# Sheet1.net
KiCad netlist of a schematic drawn in Altium Designer
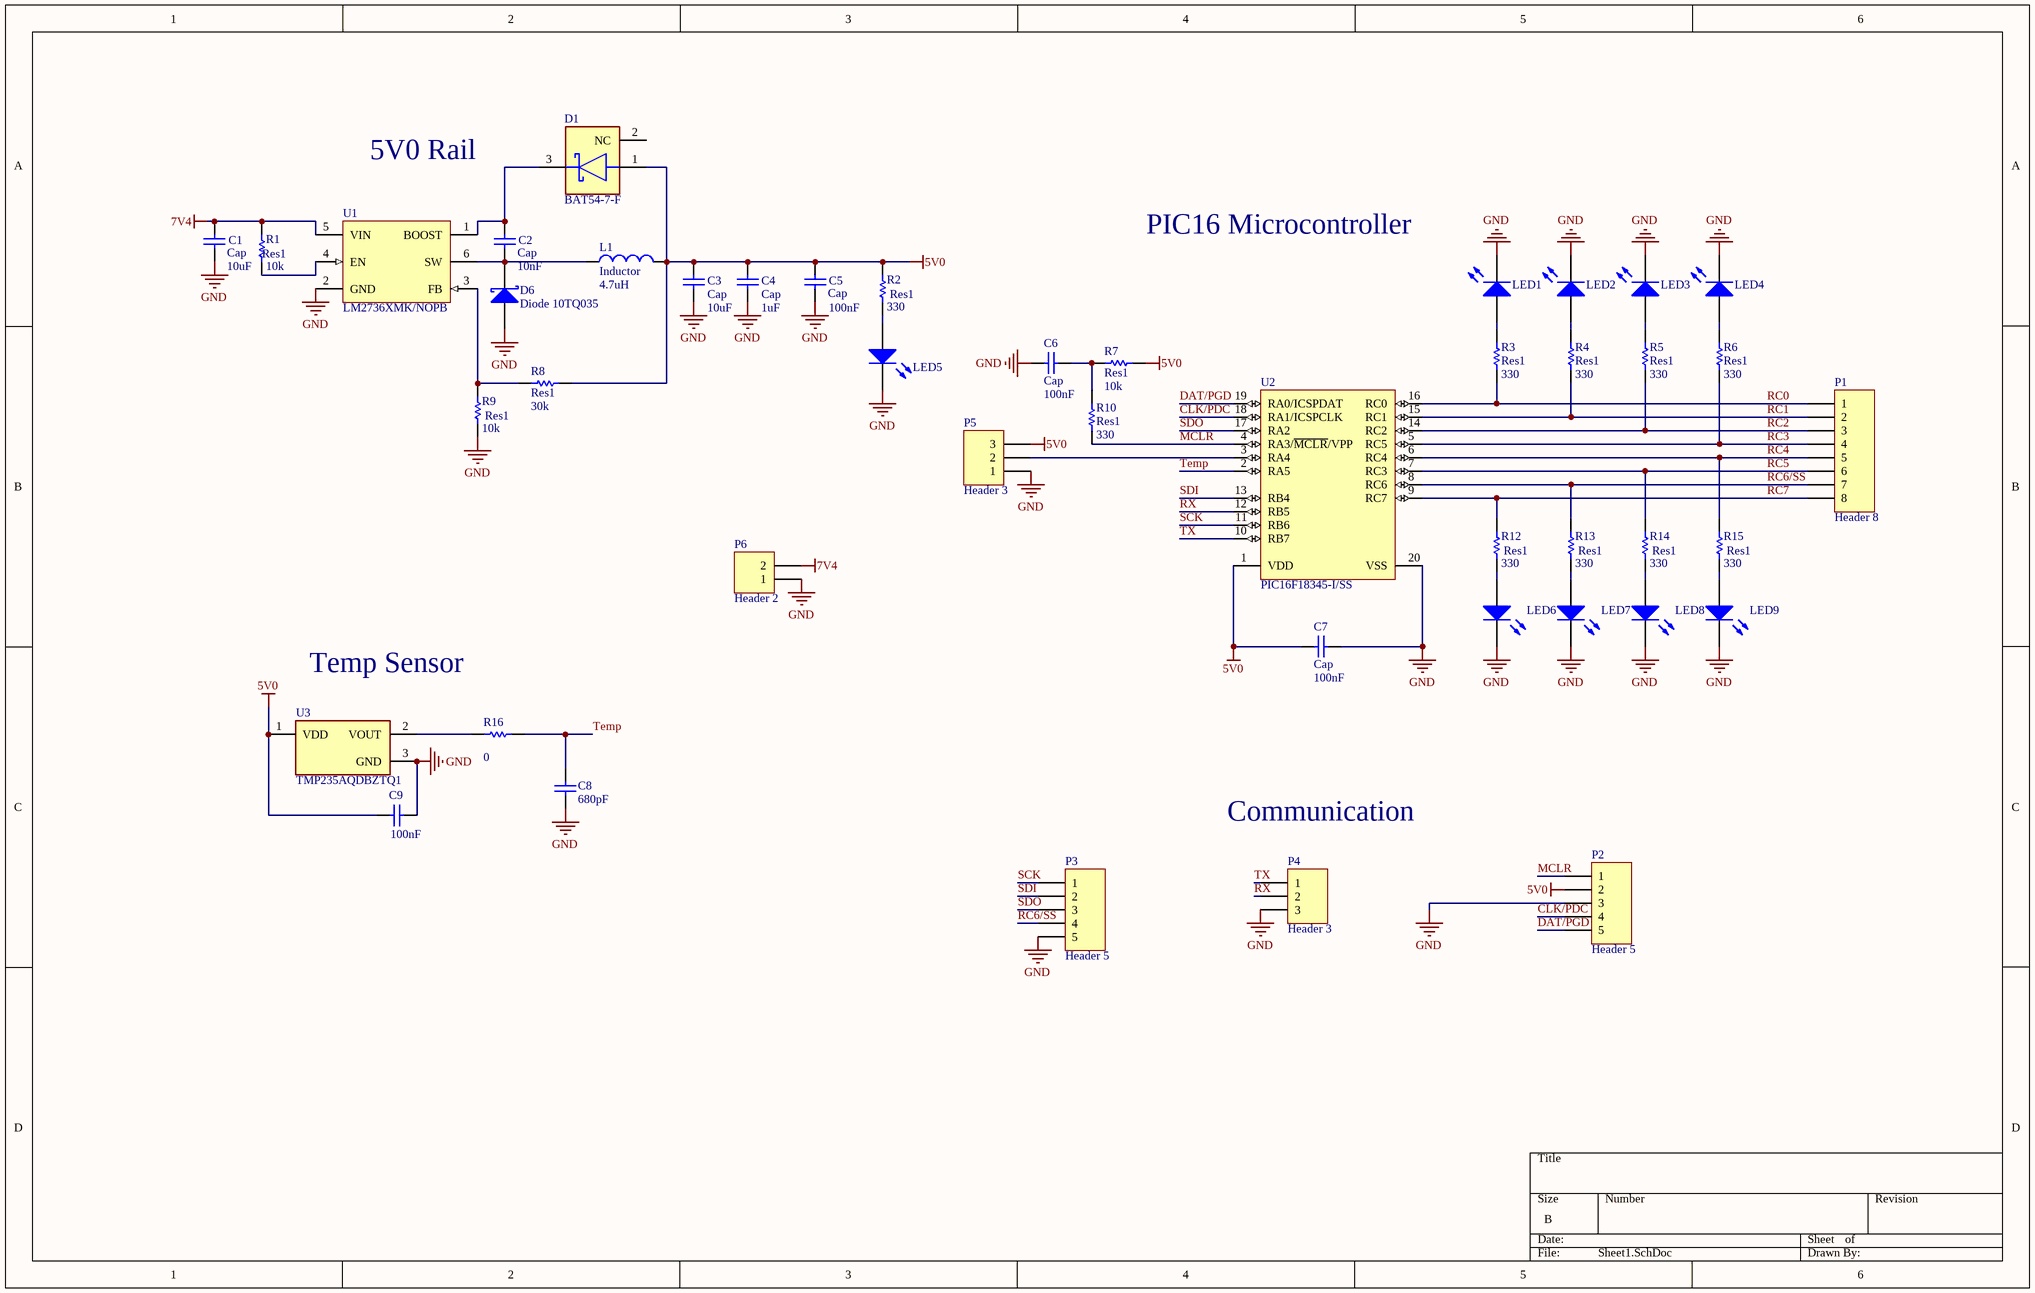
[diagram p0: Sheet1.SchDoc]

(export (version "E")
  (design (tool "Eeschema 10.0.6"))
  (components
    (comp (ref "C1")
      (value "Cap")
      (footprint "6-0805_M")
      (description "Capacitor")
      (fields (field (name "ALTIUM_VALUE") "10uF") (field (name "PUBLISHER") "Altium Limited"))
      (libsource (lib "Miscellaneous Devices") (part "Cap"))
    )
    (comp (ref "C2")
      (value "Cap")
      (footprint "6-0805_M")
      (description "Capacitor")
      (fields (field (name "ALTIUM_VALUE") "10nF") (field (name "PUBLISHER") "Altium Limited"))
      (libsource (lib "Miscellaneous Devices") (part "Cap"))
    )
    (comp (ref "C3")
      (value "Cap")
      (footprint "6-0805_M")
      (description "Capacitor")
      (fields (field (name "ALTIUM_VALUE") "10uF") (field (name "PUBLISHER") "Altium Limited"))
      (libsource (lib "Miscellaneous Devices") (part "Cap"))
    )
    (comp (ref "C4")
      (value "Cap")
      (footprint "6-0805_M")
      (description "Capacitor")
      (fields (field (name "ALTIUM_VALUE") "1uF") (field (name "PUBLISHER") "Altium Limited"))
      (libsource (lib "Miscellaneous Devices") (part "Cap"))
    )
    (comp (ref "C5")
      (value "Cap")
      (footprint "6-0805_M")
      (description "Capacitor")
      (fields (field (name "ALTIUM_VALUE") "100nF") (field (name "PUBLISHER") "Altium Limited"))
      (libsource (lib "Miscellaneous Devices") (part "Cap"))
    )
    (comp (ref "C6")
      (value "Cap")
      (footprint "6-0805_M")
      (description "Capacitor")
      (fields (field (name "ALTIUM_VALUE") "100nF") (field (name "PUBLISHER") "Altium Limited"))
      (libsource (lib "Miscellaneous Devices") (part "Cap"))
    )
    (comp (ref "C7")
      (value "Cap")
      (footprint "6-0805_M")
      (description "Capacitor")
      (fields (field (name "ALTIUM_VALUE") "100nF") (field (name "PUBLISHER") "Altium Limited"))
      (libsource (lib "Miscellaneous Devices") (part "Cap"))
    )
    (comp (ref "C8")
      (value "680pF")
      (footprint "6-0805_M")
      (description "Capacitor")
      (fields (field (name "Comment") "Cap") (field (name "PUBLISHER") "Altium Limited"))
      (libsource (lib "Miscellaneous Devices") (part "Cap"))
    )
    (comp (ref "C9")
      (value "100nF")
      (footprint "6-0805_M")
      (description "Capacitor")
      (fields (field (name "Comment") "Cap") (field (name "PUBLISHER") "Altium Limited"))
      (libsource (lib "Miscellaneous Devices") (part "Cap"))
    )
    (comp (ref "D1")
      (value "BAT54-7-F")
      (footprint "FP-SOT23-MFG")
      (description "DIODE SCHOTTKY 30V 200MA SOT23-3")
      (fields
        (field (name "MANUFACTURER") "Diodes Inc.")
        (field (name "OCTOPART") "https://octopart.com/bat54-7-f-diodes+inc.-39681803")
      )
      (libsource (lib "Altium Content Vault") (part "c46c961685e925f3e7b53c7fd0df730"))
    )
    (comp (ref "D6")
      (value "Diode 10TQ035")
      (footprint "CDBA5")
      (description "Schottky Rectifier")
      (fields (field (name "PUBLISHER") "Altium Limited"))
      (libsource (lib "Miscellaneous Devices") (part "Diode 10TQ035"))
    )
    (comp (ref "L1")
      (value "Inductor")
      (footprint "INDC2520X100N")
      (fields (field (name "ALTIUM_VALUE") "4.7uH") (field (name "PUBLISHER") "Altium Limited"))
      (libsource (lib "Miscellaneous Devices") (part "Inductor"))
    )
    (comp (ref "LED1")
      (value "150080BS75000")
      (footprint "0805_A")
      (description "SMD mono-color Chip LED, WL-SMCW, Blue")
      (fields (field (name "MANUFACTURER") "Wuerth Elektronik"))
      (libsource (lib "Altium Content Vault") (part "WE-LED_K1A2-2"))
    )
    (comp (ref "LED2")
      (value "150080BS75000")
      (footprint "0805_A")
      (description "SMD mono-color Chip LED, WL-SMCW, Blue")
      (fields (field (name "MANUFACTURER") "Wuerth Elektronik"))
      (libsource (lib "Altium Content Vault") (part "WE-LED_K1A2-2"))
    )
    (comp (ref "LED3")
      (value "150080BS75000")
      (footprint "0805_A")
      (description "SMD mono-color Chip LED, WL-SMCW, Blue")
      (fields (field (name "MANUFACTURER") "Wuerth Elektronik"))
      (libsource (lib "Altium Content Vault") (part "WE-LED_K1A2-2"))
    )
    (comp (ref "LED4")
      (value "150080BS75000")
      (footprint "0805_A")
      (description "SMD mono-color Chip LED, WL-SMCW, Blue")
      (fields (field (name "MANUFACTURER") "Wuerth Elektronik"))
      (libsource (lib "Altium Content Vault") (part "WE-LED_K1A2-2"))
    )
    (comp (ref "LED5")
      (value "150080BS75000")
      (footprint "0805_A")
      (description "SMD mono-color Chip LED, WL-SMCW, Blue")
      (fields (field (name "MANUFACTURER") "Wuerth Elektronik"))
      (libsource (lib "Altium Content Vault") (part "WE-LED_K1A2-2"))
    )
    (comp (ref "LED6")
      (value "150080BS75000")
      (footprint "0805_A")
      (description "SMD mono-color Chip LED, WL-SMCW, Blue")
      (fields (field (name "MANUFACTURER") "Wuerth Elektronik"))
      (libsource (lib "Altium Content Vault") (part "WE-LED_K1A2-2"))
    )
    (comp (ref "LED7")
      (value "150080BS75000")
      (footprint "0805_A")
      (description "SMD mono-color Chip LED, WL-SMCW, Blue")
      (fields (field (name "MANUFACTURER") "Wuerth Elektronik"))
      (libsource (lib "Altium Content Vault") (part "WE-LED_K1A2-2"))
    )
    (comp (ref "LED8")
      (value "150080BS75000")
      (footprint "0805_A")
      (description "SMD mono-color Chip LED, WL-SMCW, Blue")
      (fields (field (name "MANUFACTURER") "Wuerth Elektronik"))
      (libsource (lib "Altium Content Vault") (part "WE-LED_K1A2-2"))
    )
    (comp (ref "LED9")
      (value "150080BS75000")
      (footprint "0805_A")
      (description "SMD mono-color Chip LED, WL-SMCW, Blue")
      (fields (field (name "MANUFACTURER") "Wuerth Elektronik"))
      (libsource (lib "Altium Content Vault") (part "WE-LED_K1A2-2"))
    )
    (comp (ref "P1")
      (value "Header 8")
      (footprint "HDR1X8")
      (description "Header, 8-Pin")
      (fields (field (name "PUBLISHER") "Altium Limited"))
      (libsource (lib "Miscellaneous Connectors") (part "Header 8"))
    )
    (comp (ref "P2")
      (value "Header 5")
      (footprint "HDR1X5")
      (description "Header, 5-Pin")
      (fields (field (name "PUBLISHER") "Altium Limited"))
      (libsource (lib "Miscellaneous Connectors") (part "Header 5"))
    )
    (comp (ref "P3")
      (value "Header 5")
      (footprint "HDR1X5")
      (description "Header, 5-Pin")
      (fields (field (name "PUBLISHER") "Altium Limited"))
      (libsource (lib "Miscellaneous Connectors") (part "Header 5"))
    )
    (comp (ref "P4")
      (value "Header 3")
      (footprint "HDR1X3")
      (description "Header, 3-Pin")
      (fields (field (name "PUBLISHER") "Altium Limited"))
      (libsource (lib "") (part "Header 3_1"))
    )
    (comp (ref "P5")
      (value "Header 3")
      (footprint "HDR1X3")
      (description "Header, 3-Pin")
      (fields (field (name "PUBLISHER") "Altium Limited"))
      (libsource (lib "Miscellaneous Connectors") (part "Header 3"))
    )
    (comp (ref "P6")
      (value "Header 2")
      (footprint "HDR1X2")
      (description "Header, 2-Pin")
      (fields (field (name "PUBLISHER") "Altium Limited"))
      (libsource (lib "Miscellaneous Connectors") (part "Header 2"))
    )
    (comp (ref "R1")
      (value "Res1")
      (footprint "6-0805_M")
      (description "Resistor")
      (fields (field (name "ALTIUM_VALUE") "10k") (field (name "PUBLISHER") "Altium Limited"))
      (libsource (lib "Miscellaneous Devices") (part "Res1"))
    )
    (comp (ref "R2")
      (value "Res1")
      (footprint "6-0805_M")
      (description "Resistor")
      (fields (field (name "ALTIUM_VALUE") "330") (field (name "PUBLISHER") "Altium Limited"))
      (libsource (lib "Miscellaneous Devices") (part "Res1"))
    )
    (comp (ref "R3")
      (value "Res1")
      (footprint "6-0805_M")
      (description "Resistor")
      (fields (field (name "ALTIUM_VALUE") "330") (field (name "PUBLISHER") "Altium Limited"))
      (libsource (lib "Miscellaneous Devices") (part "Res1"))
    )
    (comp (ref "R4")
      (value "Res1")
      (footprint "6-0805_M")
      (description "Resistor")
      (fields (field (name "ALTIUM_VALUE") "330") (field (name "PUBLISHER") "Altium Limited"))
      (libsource (lib "Miscellaneous Devices") (part "Res1"))
    )
    (comp (ref "R5")
      (value "Res1")
      (footprint "6-0805_M")
      (description "Resistor")
      (fields (field (name "ALTIUM_VALUE") "330") (field (name "PUBLISHER") "Altium Limited"))
      (libsource (lib "Miscellaneous Devices") (part "Res1"))
    )
    (comp (ref "R6")
      (value "Res1")
      (footprint "6-0805_M")
      (description "Resistor")
      (fields (field (name "ALTIUM_VALUE") "330") (field (name "PUBLISHER") "Altium Limited"))
      (libsource (lib "Miscellaneous Devices") (part "Res1"))
    )
    (comp (ref "R7")
      (value "Res1")
      (footprint "6-0805_M")
      (description "Resistor")
      (fields (field (name "ALTIUM_VALUE") "10k") (field (name "PUBLISHER") "Altium Limited"))
      (libsource (lib "Miscellaneous Devices") (part "Res1"))
    )
    (comp (ref "R8")
      (value "Res1")
      (footprint "6-0805_M")
      (description "Resistor")
      (fields (field (name "ALTIUM_VALUE") "30k") (field (name "PUBLISHER") "Altium Limited"))
      (libsource (lib "Miscellaneous Devices") (part "Res1"))
    )
    (comp (ref "R9")
      (value "Res1")
      (footprint "6-0805_M")
      (description "Resistor")
      (fields (field (name "ALTIUM_VALUE") "10k") (field (name "PUBLISHER") "Altium Limited"))
      (libsource (lib "Miscellaneous Devices") (part "Res1"))
    )
    (comp (ref "R10")
      (value "Res1")
      (footprint "6-0805_M")
      (description "Resistor")
      (fields (field (name "ALTIUM_VALUE") "330") (field (name "PUBLISHER") "Altium Limited"))
      (libsource (lib "Miscellaneous Devices") (part "Res1"))
    )
    (comp (ref "R12")
      (value "Res1")
      (footprint "6-0805_M")
      (description "Resistor")
      (fields (field (name "ALTIUM_VALUE") "330") (field (name "PUBLISHER") "Altium Limited"))
      (libsource (lib "Miscellaneous Devices") (part "Res1"))
    )
    (comp (ref "R13")
      (value "Res1")
      (footprint "6-0805_M")
      (description "Resistor")
      (fields (field (name "ALTIUM_VALUE") "330") (field (name "PUBLISHER") "Altium Limited"))
      (libsource (lib "Miscellaneous Devices") (part "Res1"))
    )
    (comp (ref "R14")
      (value "Res1")
      (footprint "6-0805_M")
      (description "Resistor")
      (fields (field (name "ALTIUM_VALUE") "330") (field (name "PUBLISHER") "Altium Limited"))
      (libsource (lib "Miscellaneous Devices") (part "Res1"))
    )
    (comp (ref "R15")
      (value "Res1")
      (footprint "6-0805_M")
      (description "Resistor")
      (fields (field (name "ALTIUM_VALUE") "330") (field (name "PUBLISHER") "Altium Limited"))
      (libsource (lib "Miscellaneous Devices") (part "Res1"))
    )
    (comp (ref "R16")
      (value "0")
      (footprint "6-0805_M")
      (description "Resistor")
      (fields (field (name "Comment") "Res1") (field (name "PUBLISHER") "Altium Limited"))
      (libsource (lib "Miscellaneous Devices") (part "Res1"))
    )
    (comp (ref "U1")
      (value "LM2736XMK/NOPB")
      (footprint "DDC0006A_L")
      (description "750mA Load Step-Down DC-DC Regulator, 6-pin Tiny SOT23, Pb-Free")
      (fields (field (name "MANUFACTURER") "Texas Instruments"))
      (libsource (lib "Altium Content Vault") (part "PM-DCDC-LM2736MK"))
    )
    (comp (ref "U2")
      (value "PIC16F18345-I/SS")
      (footprint "MCHP-SS-20_V")
      (fields (field (name "MANUFACTURER") "Microchip-Technology"))
      (libsource (lib "Altium Content Vault") (part "MCHP-PIC16XF18345-20"))
    )
    (comp (ref "U3")
      (value "TMP235AQDBZTQ1")
      (footprint "FP-DBZ0003A-MFG")
      (description "LOW-POWER HIGH-ACCURACY ANALOG O")
      (fields
        (field (name "MANUFACTURER") "Texas Instruments")
        (field (name "MANUFACTURER PART NUMBER") "TMP235A2DBZR")
      )
      (libsource (lib "Altium Content Vault") (part "1212246baba8f64ab0dd7b63bd818eb"))
    )
  )
  (nets
    (net (code "1") (name "/CLK{slash}PDC") (class "Default")
      (node (ref "P2") (pin "4") (pinfunction "4_4") (pintype "passive"))
      (node (ref "U2") (pin "18") (pinfunction "RA1/ICSPCLK_18") (pintype "bidirectional"))
    )
    (net (code "2") (name "/DAT{slash}PGD") (class "Default")
      (node (ref "P2") (pin "5") (pinfunction "5_5") (pintype "passive"))
      (node (ref "U2") (pin "19") (pinfunction "RA0/ICSPDAT_19") (pintype "bidirectional"))
    )
    (net (code "3") (name "/MCLR") (class "Default")
      (node (ref "P2") (pin "1") (pinfunction "1_1") (pintype "passive"))
      (node (ref "R10") (pin "1") (pinfunction "1_1") (pintype "passive"))
      (node (ref "U2") (pin "4") (pinfunction "RA3/~{MCLR}/VPP_4") (pintype "bidirectional"))
    )
    (net (code "4") (name "/RC0") (class "Default")
      (node (ref "P1") (pin "1") (pinfunction "1_1") (pintype "passive"))
      (node (ref "R3") (pin "2") (pinfunction "2_2") (pintype "passive"))
      (node (ref "U2") (pin "16") (pinfunction "RC0_16") (pintype "bidirectional"))
    )
    (net (code "5") (name "/RC1") (class "Default")
      (node (ref "P1") (pin "2") (pinfunction "2_2") (pintype "passive"))
      (node (ref "R4") (pin "2") (pinfunction "2_2") (pintype "passive"))
      (node (ref "U2") (pin "15") (pinfunction "RC1_15") (pintype "bidirectional"))
    )
    (net (code "6") (name "/RC2") (class "Default")
      (node (ref "P1") (pin "3") (pinfunction "3_3") (pintype "passive"))
      (node (ref "R5") (pin "2") (pinfunction "2_2") (pintype "passive"))
      (node (ref "U2") (pin "14") (pinfunction "RC2_14") (pintype "bidirectional"))
    )
    (net (code "7") (name "/RC3") (class "Default")
      (node (ref "P1") (pin "4") (pinfunction "4_4") (pintype "passive"))
      (node (ref "R6") (pin "2") (pinfunction "2_2") (pintype "passive"))
      (node (ref "U2") (pin "5") (pinfunction "RC5_5") (pintype "bidirectional"))
    )
    (net (code "8") (name "/RC4") (class "Default")
      (node (ref "P1") (pin "5") (pinfunction "5_5") (pintype "passive"))
      (node (ref "R15") (pin "2") (pinfunction "2_2") (pintype "passive"))
      (node (ref "U2") (pin "6") (pinfunction "RC4_6") (pintype "bidirectional"))
    )
    (net (code "9") (name "/RC5") (class "Default")
      (node (ref "P1") (pin "6") (pinfunction "6_6") (pintype "passive"))
      (node (ref "R14") (pin "2") (pinfunction "2_2") (pintype "passive"))
      (node (ref "U2") (pin "7") (pinfunction "RC3_7") (pintype "bidirectional"))
    )
    (net (code "10") (name "/RC6{slash}SS") (class "Default")
      (node (ref "P1") (pin "7") (pinfunction "7_7") (pintype "passive"))
      (node (ref "P3") (pin "4") (pinfunction "4_4") (pintype "passive"))
      (node (ref "R13") (pin "2") (pinfunction "2_2") (pintype "passive"))
      (node (ref "U2") (pin "8") (pinfunction "RC6_8") (pintype "bidirectional"))
    )
    (net (code "11") (name "/RC7") (class "Default")
      (node (ref "P1") (pin "8") (pinfunction "8_8") (pintype "passive"))
      (node (ref "R12") (pin "2") (pinfunction "2_2") (pintype "passive"))
      (node (ref "U2") (pin "9") (pinfunction "RC7_9") (pintype "bidirectional"))
    )
    (net (code "12") (name "/RX") (class "Default")
      (node (ref "P4") (pin "2") (pinfunction "2_2") (pintype "passive"))
      (node (ref "U2") (pin "12") (pinfunction "RB5_12") (pintype "bidirectional"))
    )
    (net (code "13") (name "/SCK") (class "Default")
      (node (ref "P3") (pin "1") (pinfunction "1_1") (pintype "passive"))
      (node (ref "U2") (pin "11") (pinfunction "RB6_11") (pintype "bidirectional"))
    )
    (net (code "14") (name "/SDI") (class "Default")
      (node (ref "P3") (pin "2") (pinfunction "2_2") (pintype "passive"))
      (node (ref "U2") (pin "13") (pinfunction "RB4_13") (pintype "bidirectional"))
    )
    (net (code "15") (name "/SDO") (class "Default")
      (node (ref "P3") (pin "3") (pinfunction "3_3") (pintype "passive"))
      (node (ref "U2") (pin "17") (pinfunction "RA2_17") (pintype "bidirectional"))
    )
    (net (code "16") (name "/TX") (class "Default")
      (node (ref "P4") (pin "1") (pinfunction "1_1") (pintype "passive"))
      (node (ref "U2") (pin "10") (pinfunction "RB7_10") (pintype "bidirectional"))
    )
    (net (code "17") (name "/Temp") (class "Default")
      (node (ref "C8") (pin "1") (pinfunction "1_1") (pintype "passive"))
      (node (ref "R16") (pin "2") (pinfunction "2_2") (pintype "passive"))
      (node (ref "U2") (pin "2") (pinfunction "RA5_2") (pintype "bidirectional"))
    )
    (net (code "18") (name "5V0") (class "Default")
      (node (ref "C3") (pin "2") (pinfunction "2_2") (pintype "passive"))
      (node (ref "C4") (pin "2") (pinfunction "2_2") (pintype "passive"))
      (node (ref "C5") (pin "2") (pinfunction "2_2") (pintype "passive"))
      (node (ref "C7") (pin "2") (pinfunction "2_2") (pintype "passive"))
      (node (ref "C9") (pin "1") (pinfunction "1_1") (pintype "passive"))
      (node (ref "D1") (pin "1") (pinfunction "A_1") (pintype "passive"))
      (node (ref "L1") (pin "2") (pinfunction "2_2") (pintype "passive"))
      (node (ref "P2") (pin "2") (pinfunction "2_2") (pintype "passive"))
      (node (ref "P5") (pin "3") (pinfunction "3_3") (pintype "passive"))
      (node (ref "R2") (pin "2") (pinfunction "2_2") (pintype "passive"))
      (node (ref "R7") (pin "2") (pinfunction "2_2") (pintype "passive"))
      (node (ref "R8") (pin "1") (pinfunction "1_1") (pintype "passive"))
      (node (ref "U2") (pin "1") (pinfunction "VDD_1") (pintype "power_in"))
      (node (ref "U3") (pin "1") (pinfunction "VDD_1") (pintype "power_in"))
    )
    (net (code "19") (name "7V4") (class "Default")
      (node (ref "C1") (pin "2") (pinfunction "2_2") (pintype "passive"))
      (node (ref "P6") (pin "2") (pinfunction "2_2") (pintype "passive"))
      (node (ref "R1") (pin "2") (pinfunction "2_2") (pintype "passive"))
      (node (ref "U1") (pin "5") (pinfunction "VIN_5") (pintype "power_in"))
    )
    (net (code "20") (name "GND") (class "Default")
      (node (ref "C1") (pin "1") (pinfunction "1_1") (pintype "passive"))
      (node (ref "C3") (pin "1") (pinfunction "1_1") (pintype "passive"))
      (node (ref "C4") (pin "1") (pinfunction "1_1") (pintype "passive"))
      (node (ref "C5") (pin "1") (pinfunction "1_1") (pintype "passive"))
      (node (ref "C6") (pin "2") (pinfunction "2_2") (pintype "passive"))
      (node (ref "C7") (pin "1") (pinfunction "1_1") (pintype "passive"))
      (node (ref "C8") (pin "2") (pinfunction "2_2") (pintype "passive"))
      (node (ref "C9") (pin "2") (pinfunction "2_2") (pintype "passive"))
      (node (ref "D6") (pin "3") (pinfunction "A_3") (pintype "passive"))
      (node (ref "LED1") (pin "1") (pinfunction "K_1") (pintype "passive"))
      (node (ref "LED2") (pin "1") (pinfunction "K_1") (pintype "passive"))
      (node (ref "LED3") (pin "1") (pinfunction "K_1") (pintype "passive"))
      (node (ref "LED4") (pin "1") (pinfunction "K_1") (pintype "passive"))
      (node (ref "LED5") (pin "1") (pinfunction "K_1") (pintype "passive"))
      (node (ref "LED6") (pin "1") (pinfunction "K_1") (pintype "passive"))
      (node (ref "LED7") (pin "1") (pinfunction "K_1") (pintype "passive"))
      (node (ref "LED8") (pin "1") (pinfunction "K_1") (pintype "passive"))
      (node (ref "LED9") (pin "1") (pinfunction "K_1") (pintype "passive"))
      (node (ref "P2") (pin "3") (pinfunction "3_3") (pintype "passive"))
      (node (ref "P3") (pin "5") (pinfunction "5_5") (pintype "passive"))
      (node (ref "P4") (pin "3") (pinfunction "3_3") (pintype "passive"))
      (node (ref "P5") (pin "1") (pinfunction "1_1") (pintype "passive"))
      (node (ref "P6") (pin "1") (pinfunction "1_1") (pintype "passive"))
      (node (ref "R9") (pin "1") (pinfunction "1_1") (pintype "passive"))
      (node (ref "U1") (pin "2") (pinfunction "GND_2") (pintype "power_in"))
      (node (ref "U2") (pin "20") (pinfunction "VSS_20") (pintype "power_in"))
      (node (ref "U3") (pin "3") (pinfunction "GND_3") (pintype "power_in"))
    )
    (net (code "21") (name "Net-(C6-Pad1)") (class "Default")
      (node (ref "C6") (pin "1") (pinfunction "1_1") (pintype "passive"))
      (node (ref "R10") (pin "2") (pinfunction "2_2") (pintype "passive"))
      (node (ref "R7") (pin "1") (pinfunction "1_1") (pintype "passive"))
    )
    (net (code "22") (name "Net-(D1-C)") (class "Default")
      (node (ref "C2") (pin "2") (pinfunction "2_2") (pintype "passive"))
      (node (ref "D1") (pin "3") (pinfunction "C_3") (pintype "passive"))
      (node (ref "U1") (pin "1") (pinfunction "BOOST_1") (pintype "passive"))
    )
    (net (code "23") (name "Net-(D6-K)") (class "Default")
      (node (ref "C2") (pin "1") (pinfunction "1_1") (pintype "passive"))
      (node (ref "D6") (pin "1") (pinfunction "K_1") (pintype "passive"))
      (node (ref "L1") (pin "1") (pinfunction "1_1") (pintype "passive"))
      (node (ref "U1") (pin "6") (pinfunction "SW_6") (pintype "power_in"))
    )
    (net (code "24") (name "Net-(LED1-A)") (class "Default")
      (node (ref "LED1") (pin "2") (pinfunction "A_2") (pintype "passive"))
      (node (ref "R3") (pin "1") (pinfunction "1_1") (pintype "passive"))
    )
    (net (code "25") (name "Net-(LED2-A)") (class "Default")
      (node (ref "LED2") (pin "2") (pinfunction "A_2") (pintype "passive"))
      (node (ref "R4") (pin "1") (pinfunction "1_1") (pintype "passive"))
    )
    (net (code "26") (name "Net-(LED3-A)") (class "Default")
      (node (ref "LED3") (pin "2") (pinfunction "A_2") (pintype "passive"))
      (node (ref "R5") (pin "1") (pinfunction "1_1") (pintype "passive"))
    )
    (net (code "27") (name "Net-(LED4-A)") (class "Default")
      (node (ref "LED4") (pin "2") (pinfunction "A_2") (pintype "passive"))
      (node (ref "R6") (pin "1") (pinfunction "1_1") (pintype "passive"))
    )
    (net (code "28") (name "Net-(LED5-A)") (class "Default")
      (node (ref "LED5") (pin "2") (pinfunction "A_2") (pintype "passive"))
      (node (ref "R2") (pin "1") (pinfunction "1_1") (pintype "passive"))
    )
    (net (code "29") (name "Net-(LED6-A)") (class "Default")
      (node (ref "LED6") (pin "2") (pinfunction "A_2") (pintype "passive"))
      (node (ref "R12") (pin "1") (pinfunction "1_1") (pintype "passive"))
    )
    (net (code "30") (name "Net-(LED7-A)") (class "Default")
      (node (ref "LED7") (pin "2") (pinfunction "A_2") (pintype "passive"))
      (node (ref "R13") (pin "1") (pinfunction "1_1") (pintype "passive"))
    )
    (net (code "31") (name "Net-(LED8-A)") (class "Default")
      (node (ref "LED8") (pin "2") (pinfunction "A_2") (pintype "passive"))
      (node (ref "R14") (pin "1") (pinfunction "1_1") (pintype "passive"))
    )
    (net (code "32") (name "Net-(LED9-A)") (class "Default")
      (node (ref "LED9") (pin "2") (pinfunction "A_2") (pintype "passive"))
      (node (ref "R15") (pin "1") (pinfunction "1_1") (pintype "passive"))
    )
    (net (code "33") (name "Net-(U1-EN)") (class "Default")
      (node (ref "R1") (pin "1") (pinfunction "1_1") (pintype "passive"))
      (node (ref "U1") (pin "4") (pinfunction "EN_4") (pintype "input"))
    )
    (net (code "34") (name "Net-(U1-FB)") (class "Default")
      (node (ref "R8") (pin "2") (pinfunction "2_2") (pintype "passive"))
      (node (ref "R9") (pin "2") (pinfunction "2_2") (pintype "passive"))
      (node (ref "U1") (pin "3") (pinfunction "FB_3") (pintype "input"))
    )
    (net (code "35") (name "Net-(U2-RA4)") (class "Default")
      (node (ref "P5") (pin "2") (pinfunction "2_2") (pintype "passive"))
      (node (ref "U2") (pin "3") (pinfunction "RA4_3") (pintype "bidirectional"))
    )
    (net (code "36") (name "Net-(U3-VOUT)") (class "Default")
      (node (ref "R16") (pin "1") (pinfunction "1_1") (pintype "passive"))
      (node (ref "U3") (pin "2") (pinfunction "VOUT_2") (pintype "passive"))
    )
    (net (code "37") (name "unconnected-(D1-NC-Pad2)") (class "Default")
      (node (ref "D1") (pin "2") (pinfunction "NC_2") (pintype "passive"))
    )
  )
)
